# 3_1.net
KiCad netlist of a schematic drawn in Altium Designer
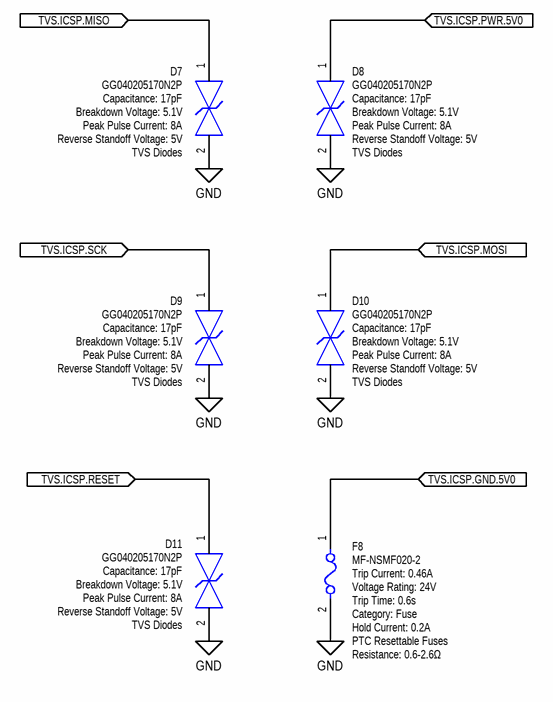
[diagram p0: Блок3.1.SchDoc]

(export (version "E")
  (design (tool "Eeschema 10.0.6"))
  (components
    (comp (ref "D7")
      (value "GG040205170N2P")
      (footprint "FP-GG0402-IPC_A")
      (description "TVS DIODE 5V 10V 0402")
      (fields
        (field (name "OCTOPART") "https://octopart.com/gg040205170n2p-avx-81066082")
        (field (name "CAPACITANCE") "17pF")
        (field (name "MANUFACTURER") "AVX")
        (field (name "BREAKDOWN VOLTAGE") "5.1V")
        (field (name "PEAK PULSE CURRENT") "8A")
        (field (name "REVERSE STANDOFF VOLTAGE") "5V")
        (field (name "DEVICE CLASS L2") "TVS Diodes")
      )
      (libsource (lib "Altium Content Vault") (part "11bd9d59d340f0612179daf16ad9b72"))
    )
    (comp (ref "D8")
      (value "GG040205170N2P")
      (footprint "FP-GG0402-IPC_A")
      (description "TVS DIODE 5V 10V 0402")
      (fields
        (field (name "OCTOPART") "https://octopart.com/gg040205170n2p-avx-81066082")
        (field (name "CAPACITANCE") "17pF")
        (field (name "MANUFACTURER") "AVX")
        (field (name "BREAKDOWN VOLTAGE") "5.1V")
        (field (name "PEAK PULSE CURRENT") "8A")
        (field (name "REVERSE STANDOFF VOLTAGE") "5V")
        (field (name "DEVICE CLASS L2") "TVS Diodes")
      )
      (libsource (lib "Altium Content Vault") (part "11bd9d59d340f0612179daf16ad9b72"))
    )
    (comp (ref "D9")
      (value "GG040205170N2P")
      (footprint "FP-GG0402-IPC_A")
      (description "TVS DIODE 5V 10V 0402")
      (fields
        (field (name "OCTOPART") "https://octopart.com/gg040205170n2p-avx-81066082")
        (field (name "CAPACITANCE") "17pF")
        (field (name "MANUFACTURER") "AVX")
        (field (name "BREAKDOWN VOLTAGE") "5.1V")
        (field (name "PEAK PULSE CURRENT") "8A")
        (field (name "REVERSE STANDOFF VOLTAGE") "5V")
        (field (name "DEVICE CLASS L2") "TVS Diodes")
      )
      (libsource (lib "Altium Content Vault") (part "11bd9d59d340f0612179daf16ad9b72"))
    )
    (comp (ref "D10")
      (value "GG040205170N2P")
      (footprint "FP-GG0402-IPC_A")
      (description "TVS DIODE 5V 10V 0402")
      (fields
        (field (name "OCTOPART") "https://octopart.com/gg040205170n2p-avx-81066082")
        (field (name "CAPACITANCE") "17pF")
        (field (name "MANUFACTURER") "AVX")
        (field (name "BREAKDOWN VOLTAGE") "5.1V")
        (field (name "PEAK PULSE CURRENT") "8A")
        (field (name "REVERSE STANDOFF VOLTAGE") "5V")
        (field (name "DEVICE CLASS L2") "TVS Diodes")
      )
      (libsource (lib "Altium Content Vault") (part "11bd9d59d340f0612179daf16ad9b72"))
    )
    (comp (ref "D11")
      (value "GG040205170N2P")
      (footprint "FP-GG0402-IPC_A")
      (description "TVS DIODE 5V 10V 0402")
      (fields
        (field (name "OCTOPART") "https://octopart.com/gg040205170n2p-avx-81066082")
        (field (name "CAPACITANCE") "17pF")
        (field (name "MANUFACTURER") "AVX")
        (field (name "BREAKDOWN VOLTAGE") "5.1V")
        (field (name "PEAK PULSE CURRENT") "8A")
        (field (name "REVERSE STANDOFF VOLTAGE") "5V")
        (field (name "DEVICE CLASS L2") "TVS Diodes")
      )
      (libsource (lib "Altium Content Vault") (part "11bd9d59d340f0612179daf16ad9b72"))
    )
    (comp (ref "F8")
      (value "MF-NSMF020-2")
      (footprint "FP-MF-NSMF020-2-MFG")
      (description "PTC RESET FUSE 24V 200MA 1206")
      (fields
        (field (name "TRIP CURRENT") "0.46A")
        (field (name "VOLTAGE RATING") "24V")
        (field (name "TRIP TIME") "0.6s")
        (field (name "CATEGORY") "Fuse")
        (field (name "HOLD CURRENT") "0.2A")
        (field (name "DEVICE CLASS L2") "PTC Resettable Fuses")
        (field (name "MANUFACTURER") "Bourns")
        (field (name "OCTOPART") "https://octopart.com/mf-nsmf020-2-bourns-94649")
        (field (name "RESISTANCE") "0.6-2.6Ω")
      )
      (libsource (lib "Altium Content Vault") (part "5bcf9b9f640e542cf0359d10258e979"))
    )
  )
  (nets
    (net (code "1") (name "/TVS.ICSP.GND.5V0") (class "Default")
      (node (ref "F8") (pin "1") (pinfunction "1_1") (pintype "passive"))
    )
    (net (code "2") (name "/TVS.ICSP.MISO") (class "Default")
      (node (ref "D7") (pin "1") (pinfunction "1_1") (pintype "passive"))
    )
    (net (code "3") (name "/TVS.ICSP.MOSI") (class "Default")
      (node (ref "D10") (pin "1") (pinfunction "1_1") (pintype "passive"))
    )
    (net (code "4") (name "/TVS.ICSP.PWR.5V0") (class "Default")
      (node (ref "D8") (pin "1") (pinfunction "1_1") (pintype "passive"))
    )
    (net (code "5") (name "/TVS.ICSP.RESET") (class "Default")
      (node (ref "D11") (pin "1") (pinfunction "1_1") (pintype "passive"))
    )
    (net (code "6") (name "/TVS.ICSP.SCK") (class "Default")
      (node (ref "D9") (pin "1") (pinfunction "1_1") (pintype "passive"))
    )
    (net (code "7") (name "GND") (class "Default")
      (node (ref "D10") (pin "2") (pinfunction "2_2") (pintype "passive"))
      (node (ref "D11") (pin "2") (pinfunction "2_2") (pintype "passive"))
      (node (ref "D7") (pin "2") (pinfunction "2_2") (pintype "passive"))
      (node (ref "D8") (pin "2") (pinfunction "2_2") (pintype "passive"))
      (node (ref "D9") (pin "2") (pinfunction "2_2") (pintype "passive"))
      (node (ref "F8") (pin "2") (pinfunction "2_2") (pintype "passive"))
    )
  )
)
